# RPI_Hat_ID.net
KiCad netlist of a schematic drawn in Altium Designer
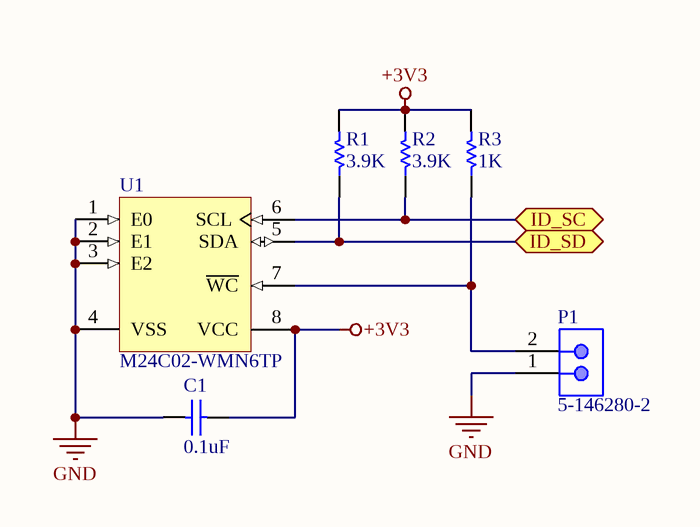
[diagram p0: RPI Hat ID.SchDoc]

(export (version "E")
  (design (tool "Eeschema 10.0.6"))
  (components
    (comp (ref "C1")
      (value "0.1uF")
      (footprint "CAPC1608X87X35NL15T15")
      (fields (field (name "PART NUMBER") "C0603X104K5RACTU") (field (name "MANUFACTURER") "Kemet"))
      (libsource (lib "Altium Content Vault") (part "CAP"))
    )
    (comp (ref "P1")
      (value "5-146280-2")
      (footprint "TECO-5-146280-2_V")
      (fields (field (name "MANUFACTURER") "TE Connectivity"))
      (libsource (lib "Altium Content Vault") (part "CN-1P-M-R2"))
    )
    (comp (ref "R1")
      (value "3.9K")
      (footprint "RESC1608X55X30ML15T15")
      (fields (field (name "PART NUMBER") "ERJ-3EKF1001V") (field (name "MANUFACTURER") "Panasonic"))
      (libsource (lib "Altium Content Vault") (part "RES"))
    )
    (comp (ref "R2")
      (value "3.9K")
      (footprint "RESC1608X55X30ML15T15")
      (fields (field (name "PART NUMBER") "ERJ-3EKF1001V") (field (name "MANUFACTURER") "Panasonic"))
      (libsource (lib "Altium Content Vault") (part "RES"))
    )
    (comp (ref "R3")
      (value "1K")
      (footprint "RESC1608X55X30ML15T15")
      (fields (field (name "PART NUMBER") "ERJ-3EKF1001V") (field (name "MANUFACTURER") "Panasonic"))
      (libsource (lib "Altium Content Vault") (part "RES"))
    )
    (comp (ref "U1")
      (value "M24C02-WMN6TP")
      (footprint "STM-M24C02-WMN6TP-8_M")
      (description "EEPROM Serial-I2C, 2Kbit, 2.5 to 5.5 V, 400 kHz, 8-Pin SO, -40 to 85 degC, RoHS, Tape and Reel")
      (fields (field (name "MANUFACTURER") "STMicroelectronics"))
      (libsource (lib "Altium Content Vault") (part "STM-M24C02-WMN6TP-8"))
    )
  )
  (nets
    (net (code "1") (name "+3V3") (class "Default")
      (node (ref "C1") (pin "1") (pinfunction "1_1") (pintype "passive"))
      (node (ref "R1") (pin "2") (pinfunction "2_2") (pintype "passive"))
      (node (ref "R2") (pin "2") (pinfunction "2_2") (pintype "passive"))
      (node (ref "R3") (pin "2") (pinfunction "2_2") (pintype "passive"))
      (node (ref "U1") (pin "8") (pinfunction "VCC_8") (pintype "power_in"))
    )
    (net (code "2") (name "/ID_SC") (class "Default")
      (node (ref "R2") (pin "1") (pinfunction "1_1") (pintype "passive"))
      (node (ref "U1") (pin "6") (pinfunction "SCL_6") (pintype "input"))
    )
    (net (code "3") (name "/ID_SD") (class "Default")
      (node (ref "R1") (pin "1") (pinfunction "1_1") (pintype "passive"))
      (node (ref "U1") (pin "5") (pinfunction "SDA_5") (pintype "bidirectional"))
    )
    (net (code "4") (name "GND") (class "Default")
      (node (ref "C1") (pin "2") (pinfunction "2_2") (pintype "passive"))
      (node (ref "P1") (pin "1") (pinfunction "1_1") (pintype "passive"))
      (node (ref "U1") (pin "1") (pinfunction "E0_1") (pintype "input"))
      (node (ref "U1") (pin "2") (pinfunction "E1_2") (pintype "input"))
      (node (ref "U1") (pin "3") (pinfunction "E2_3") (pintype "input"))
      (node (ref "U1") (pin "4") (pinfunction "VSS_4") (pintype "power_in"))
    )
    (net (code "5") (name "Net-(U1-~{WC})") (class "Default")
      (node (ref "P1") (pin "2") (pinfunction "2_2") (pintype "passive"))
      (node (ref "R3") (pin "1") (pinfunction "1_1") (pintype "passive"))
      (node (ref "U1") (pin "7") (pinfunction "~{WC}_7") (pintype "input"))
    )
  )
)
